# poll_anlysr_sch.net
KiCad netlist of a schematic drawn in Altium Designer
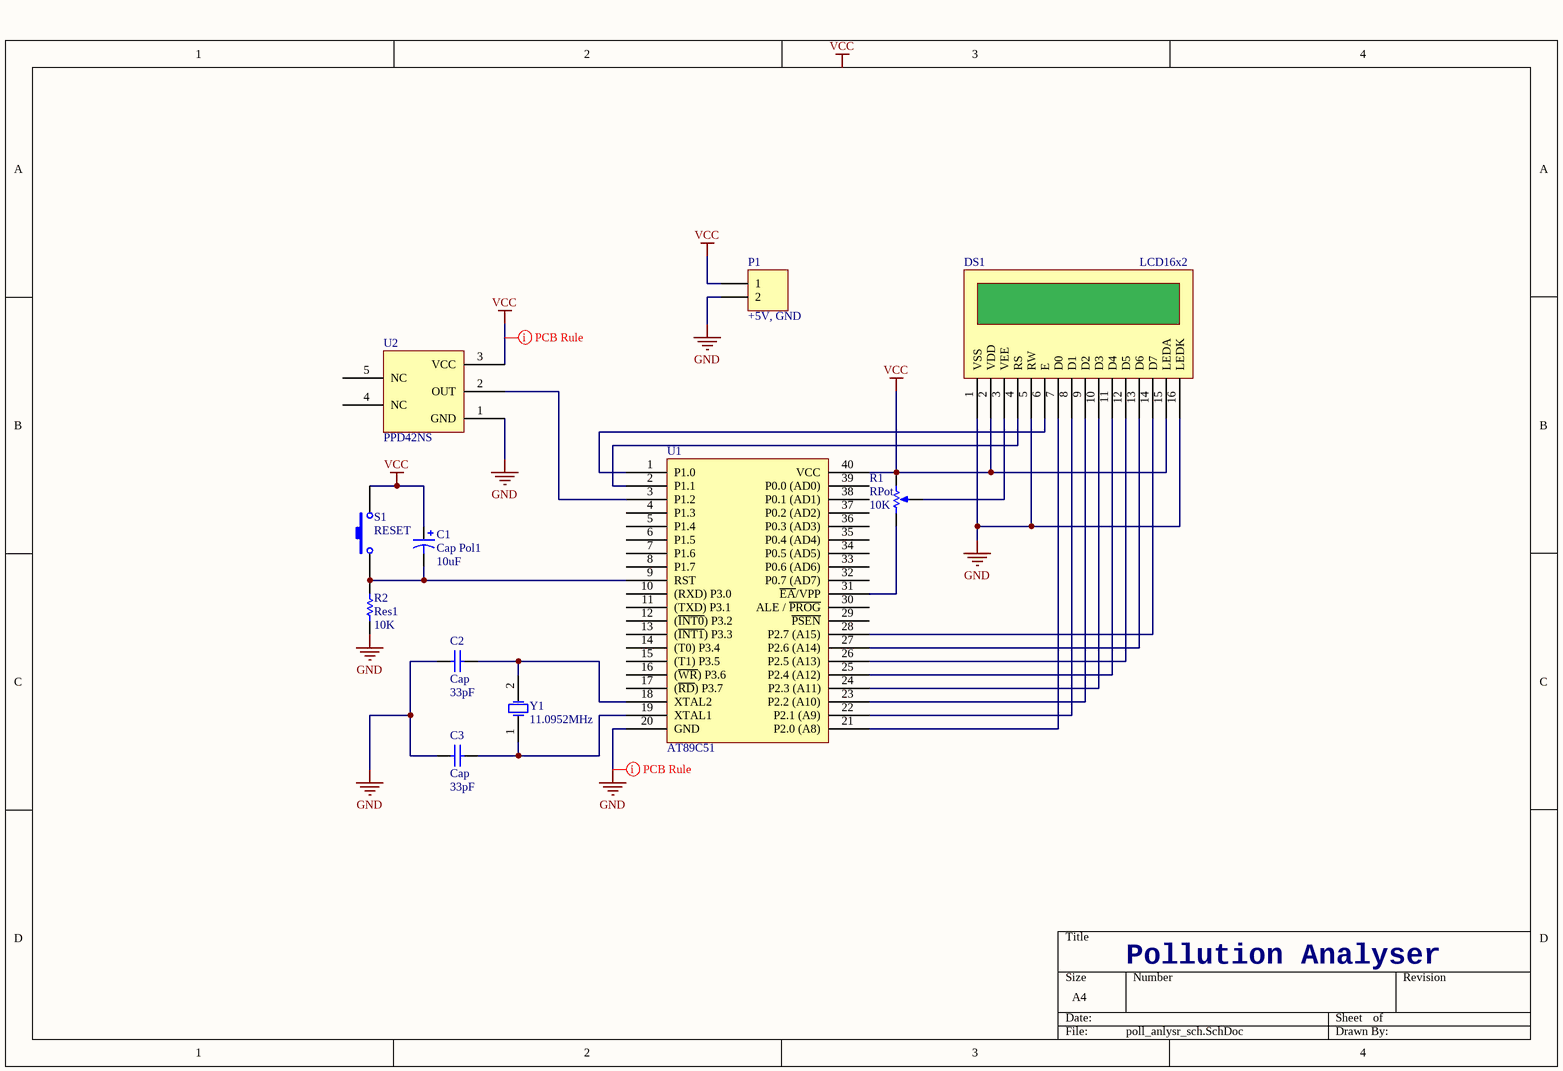
[diagram p0: poll_anlysr_sch.SchDoc]

(export (version "E")
  (design (tool "Eeschema 10.0.6"))
  (components
    (comp (ref "C1")
      (value "Cap Pol1")
      (footprint "CAPR5-4X5")
      (description "Polarized Capacitor")
      (fields (field (name "ALTIUM_VALUE") "10uF") (field (name "PUBLISHER") "Altium Limited"))
      (libsource (lib "Miscellaneous Devices") (part "Cap Pol1"))
    )
    (comp (ref "C2")
      (value "Cap")
      (footprint "CAPR5-4X5")
      (description "Capacitor")
      (fields (field (name "ALTIUM_VALUE") "33pF") (field (name "PUBLISHER") "Altium Limited"))
      (libsource (lib "Miscellaneous Devices") (part "Cap"))
    )
    (comp (ref "C3")
      (value "Cap")
      (footprint "CAPR5-4X5")
      (description "Capacitor")
      (fields (field (name "ALTIUM_VALUE") "33pF") (field (name "PUBLISHER") "Altium Limited"))
      (libsource (lib "Miscellaneous Devices") (part "Cap"))
    )
    (comp (ref "DS1")
      (value "LCD16x2")
      (footprint "LCD_16x2")
      (description "Dsiplay")
      (libsource (lib "LCD_16x2_sch") (part "LCD16x2"))
    )
    (comp (ref "P1")
      (value "+5V, GND")
      (footprint "HDR1X2")
      (description "2-Pin Header")
      (fields (field (name "PUBLISHER") "Altium Limited"))
      (libsource (lib "Miscellaneous Connectors") (part "Header 2"))
    )
    (comp (ref "R1")
      (value "RPot")
      (footprint "Rpot")
      (description "Potentiometer")
      (fields (field (name "ALTIUM_VALUE") "10K") (field (name "PUBLISHER") "Altium Limited"))
      (libsource (lib "Miscellaneous Devices") (part "RPot"))
    )
    (comp (ref "R2")
      (value "Res1")
      (footprint "AXIAL-0.3")
      (description "Resistor")
      (fields (field (name "ALTIUM_VALUE") "10K") (field (name "PUBLISHER") "Altium Limited"))
      (libsource (lib "Miscellaneous Devices") (part "Res1"))
    )
    (comp (ref "S1")
      (value "RESET")
      (footprint "SWpush")
      (description "Switch")
      (fields (field (name "PUBLISHER") "Altium Limited"))
      (libsource (lib "Miscellaneous Devices") (part "SW-PB"))
    )
    (comp (ref "U1")
      (value "AT89C51")
      (footprint "AT89C51")
      (description "8-bit uC")
      (libsource (lib "AT89C51_sch") (part "AT89C51"))
    )
    (comp (ref "U2")
      (value "PPD42NS")
      (footprint "PPD42NS")
      (description "Dust Sensor")
      (libsource (lib "PPD42NS_sch") (part "PPD42NS"))
    )
    (comp (ref "Y1")
      (value "11.0952MHz")
      (footprint "HC-49U")
      (description "Crystal Oscillator")
      (fields (field (name "PUBLISHER") "Altium Limited"))
      (libsource (lib "Miscellaneous Devices") (part "XTAL"))
    )
  )
  (nets
    (net (code "1") (name "GND") (class "Default")
      (node (ref "C2") (pin "1") (pinfunction "1_1") (pintype "passive"))
      (node (ref "C3") (pin "1") (pinfunction "1_1") (pintype "passive"))
      (node (ref "DS1") (pin "1") (pinfunction "VSS_1") (pintype "passive"))
      (node (ref "DS1") (pin "16") (pinfunction "LEDK_16") (pintype "passive"))
      (node (ref "DS1") (pin "5") (pinfunction "RW_5") (pintype "passive"))
      (node (ref "P1") (pin "2") (pinfunction "2_2") (pintype "passive"))
      (node (ref "R2") (pin "2") (pinfunction "2_2") (pintype "passive"))
      (node (ref "U1") (pin "20") (pinfunction "GND_20") (pintype "passive"))
      (node (ref "U2") (pin "1") (pinfunction "GND_1") (pintype "passive"))
    )
    (net (code "2") (name "Net-(DS1-D0)") (class "Default")
      (node (ref "DS1") (pin "7") (pinfunction "D0_7") (pintype "passive"))
      (node (ref "U1") (pin "21") (pinfunction "P2.0_(A8)_21") (pintype "passive"))
    )
    (net (code "3") (name "Net-(DS1-D1)") (class "Default")
      (node (ref "DS1") (pin "8") (pinfunction "D1_8") (pintype "passive"))
      (node (ref "U1") (pin "22") (pinfunction "P2.1_(A9)_22") (pintype "passive"))
    )
    (net (code "4") (name "Net-(DS1-D2)") (class "Default")
      (node (ref "DS1") (pin "9") (pinfunction "D2_9") (pintype "passive"))
      (node (ref "U1") (pin "23") (pinfunction "P2.2_(A10)_23") (pintype "passive"))
    )
    (net (code "5") (name "Net-(DS1-D3)") (class "Default")
      (node (ref "DS1") (pin "10") (pinfunction "D3_10") (pintype "passive"))
      (node (ref "U1") (pin "24") (pinfunction "P2.3_(A11)_24") (pintype "passive"))
    )
    (net (code "6") (name "Net-(DS1-D4)") (class "Default")
      (node (ref "DS1") (pin "11") (pinfunction "D4_11") (pintype "passive"))
      (node (ref "U1") (pin "25") (pinfunction "P2.4_(A12)_25") (pintype "passive"))
    )
    (net (code "7") (name "Net-(DS1-D5)") (class "Default")
      (node (ref "DS1") (pin "12") (pinfunction "D5_12") (pintype "passive"))
      (node (ref "U1") (pin "26") (pinfunction "P2.5_(A13)_26") (pintype "passive"))
    )
    (net (code "8") (name "Net-(DS1-D6)") (class "Default")
      (node (ref "DS1") (pin "13") (pinfunction "D6_13") (pintype "passive"))
      (node (ref "U1") (pin "27") (pinfunction "P2.6_(A14)_27") (pintype "passive"))
    )
    (net (code "9") (name "Net-(DS1-D7)") (class "Default")
      (node (ref "DS1") (pin "14") (pinfunction "D7_14") (pintype "passive"))
      (node (ref "U1") (pin "28") (pinfunction "P2.7_(A15)_28") (pintype "passive"))
    )
    (net (code "10") (name "Net-(DS1-E)") (class "Default")
      (node (ref "DS1") (pin "6") (pinfunction "E_6") (pintype "passive"))
      (node (ref "U1") (pin "1") (pinfunction "P1.0_1") (pintype "passive"))
    )
    (net (code "11") (name "Net-(DS1-RS)") (class "Default")
      (node (ref "DS1") (pin "4") (pinfunction "RS_4") (pintype "passive"))
      (node (ref "U1") (pin "2") (pinfunction "P1.1_2") (pintype "passive"))
    )
    (net (code "12") (name "Net-(DS1-VEE)") (class "Default")
      (node (ref "DS1") (pin "3") (pinfunction "VEE_3") (pintype "passive"))
      (node (ref "R1") (pin "3") (pinfunction "TAP_3") (pintype "passive"))
    )
    (net (code "13") (name "Net-(R1-TOP)") (class "Default")
      (node (ref "R1") (pin "1") (pinfunction "TOP_1") (pintype "passive"))
      (node (ref "U1") (pin "31") (pinfunction "~{EA}/VPP_31") (pintype "passive"))
    )
    (net (code "14") (name "Net-(U1-P1.2)") (class "Default")
      (node (ref "U1") (pin "3") (pinfunction "P1.2_3") (pintype "passive"))
      (node (ref "U2") (pin "2") (pinfunction "OUT_2") (pintype "passive"))
    )
    (net (code "15") (name "Net-(U1-RST)") (class "Default")
      (node (ref "C1") (pin "2") (pinfunction "2_2") (pintype "passive"))
      (node (ref "R2") (pin "1") (pinfunction "1_1") (pintype "passive"))
      (node (ref "S1") (pin "1") (pinfunction "1_1") (pintype "passive"))
      (node (ref "U1") (pin "9") (pinfunction "RST_9") (pintype "passive"))
    )
    (net (code "16") (name "Net-(U1-XTAL1)") (class "Default")
      (node (ref "C3") (pin "2") (pinfunction "2_2") (pintype "passive"))
      (node (ref "U1") (pin "19") (pinfunction "XTAL1_19") (pintype "passive"))
      (node (ref "Y1") (pin "1") (pinfunction "OSC1_1") (pintype "passive"))
    )
    (net (code "17") (name "Net-(U1-XTAL2)") (class "Default")
      (node (ref "C2") (pin "2") (pinfunction "2_2") (pintype "passive"))
      (node (ref "U1") (pin "18") (pinfunction "XTAL2_18") (pintype "passive"))
      (node (ref "Y1") (pin "2") (pinfunction "OSC2_2") (pintype "passive"))
    )
    (net (code "18") (name "VCC") (class "Default")
      (node (ref "C1") (pin "1") (pinfunction "1_1") (pintype "passive"))
      (node (ref "DS1") (pin "15") (pinfunction "LEDA_15") (pintype "passive"))
      (node (ref "DS1") (pin "2") (pinfunction "VDD_2") (pintype "passive"))
      (node (ref "P1") (pin "1") (pinfunction "1_1") (pintype "passive"))
      (node (ref "R1") (pin "2") (pinfunction "BOT_2") (pintype "passive"))
      (node (ref "S1") (pin "2") (pinfunction "2_2") (pintype "passive"))
      (node (ref "U1") (pin "40") (pinfunction "VCC_40") (pintype "passive"))
      (node (ref "U2") (pin "3") (pinfunction "VCC_3") (pintype "passive"))
    )
    (net (code "19") (name "unconnected-(U1-(RXD)_P3.0-Pad10)") (class "Default")
      (node (ref "U1") (pin "10") (pinfunction "(RXD)_P3.0_10") (pintype "passive"))
    )
    (net (code "20") (name "unconnected-(U1-(T0)_P3.4-Pad14)") (class "Default")
      (node (ref "U1") (pin "14") (pinfunction "(T0)_P3.4_14") (pintype "passive"))
    )
    (net (code "21") (name "unconnected-(U1-(T1)_P3.5-Pad15)") (class "Default")
      (node (ref "U1") (pin "15") (pinfunction "(T1)_P3.5_15") (pintype "passive"))
    )
    (net (code "22") (name "unconnected-(U1-(TXD)_P3.1-Pad11)") (class "Default")
      (node (ref "U1") (pin "11") (pinfunction "(TXD)_P3.1_11") (pintype "passive"))
    )
    (net (code "23") (name "unconnected-(U1-(~{INT0})_P3.2-Pad12)") (class "Default")
      (node (ref "U1") (pin "12") (pinfunction "(~{INT0})_P3.2_12") (pintype "passive"))
    )
    (net (code "24") (name "unconnected-(U1-(~{INT1})_P3.3-Pad13)") (class "Default")
      (node (ref "U1") (pin "13") (pinfunction "(~{INT1})_P3.3_13") (pintype "passive"))
    )
    (net (code "25") (name "unconnected-(U1-(~{RD})_P3.7-Pad17)") (class "Default")
      (node (ref "U1") (pin "17") (pinfunction "(~{RD})_P3.7_17") (pintype "passive"))
    )
    (net (code "26") (name "unconnected-(U1-(~{WR})_P3.6-Pad16)") (class "Default")
      (node (ref "U1") (pin "16") (pinfunction "(~{WR})_P3.6_16") (pintype "passive"))
    )
    (net (code "27") (name "unconnected-(U1-ALE_{slash}_~{PROG}-Pad30)") (class "Default")
      (node (ref "U1") (pin "30") (pinfunction "ALE_/_~{PROG}_30") (pintype "passive"))
    )
    (net (code "28") (name "unconnected-(U1-P0.0_(AD0)-Pad39)") (class "Default")
      (node (ref "U1") (pin "39") (pinfunction "P0.0_(AD0)_39") (pintype "passive"))
    )
    (net (code "29") (name "unconnected-(U1-P0.1_(AD1)-Pad38)") (class "Default")
      (node (ref "U1") (pin "38") (pinfunction "P0.1_(AD1)_38") (pintype "power_in"))
    )
    (net (code "30") (name "unconnected-(U1-P0.2_(AD2)-Pad37)") (class "Default")
      (node (ref "U1") (pin "37") (pinfunction "P0.2_(AD2)_37") (pintype "passive"))
    )
    (net (code "31") (name "unconnected-(U1-P0.3_(AD3)-Pad36)") (class "Default")
      (node (ref "U1") (pin "36") (pinfunction "P0.3_(AD3)_36") (pintype "passive"))
    )
    (net (code "32") (name "unconnected-(U1-P0.4_(AD4)-Pad35)") (class "Default")
      (node (ref "U1") (pin "35") (pinfunction "P0.4_(AD4)_35") (pintype "passive"))
    )
    (net (code "33") (name "unconnected-(U1-P0.5_(AD5)-Pad34)") (class "Default")
      (node (ref "U1") (pin "34") (pinfunction "P0.5_(AD5)_34") (pintype "passive"))
    )
    (net (code "34") (name "unconnected-(U1-P0.6_(AD6)-Pad33)") (class "Default")
      (node (ref "U1") (pin "33") (pinfunction "P0.6_(AD6)_33") (pintype "passive"))
    )
    (net (code "35") (name "unconnected-(U1-P0.7_(AD7)-Pad32)") (class "Default")
      (node (ref "U1") (pin "32") (pinfunction "P0.7_(AD7)_32") (pintype "passive"))
    )
    (net (code "36") (name "unconnected-(U1-P1.3-Pad4)") (class "Default")
      (node (ref "U1") (pin "4") (pinfunction "P1.3_4") (pintype "passive"))
    )
    (net (code "37") (name "unconnected-(U1-P1.4-Pad5)") (class "Default")
      (node (ref "U1") (pin "5") (pinfunction "P1.4_5") (pintype "passive"))
    )
    (net (code "38") (name "unconnected-(U1-P1.5-Pad6)") (class "Default")
      (node (ref "U1") (pin "6") (pinfunction "P1.5_6") (pintype "passive"))
    )
    (net (code "39") (name "unconnected-(U1-P1.6-Pad7)") (class "Default")
      (node (ref "U1") (pin "7") (pinfunction "P1.6_7") (pintype "passive"))
    )
    (net (code "40") (name "unconnected-(U1-P1.7-Pad8)") (class "Default")
      (node (ref "U1") (pin "8") (pinfunction "P1.7_8") (pintype "passive"))
    )
    (net (code "41") (name "unconnected-(U1-~{PSEN}-Pad29)") (class "Default")
      (node (ref "U1") (pin "29") (pinfunction "~{PSEN}_29") (pintype "passive"))
    )
    (net (code "42") (name "unconnected-(U2-NC-Pad4)") (class "Default")
      (node (ref "U2") (pin "4") (pinfunction "NC_4") (pintype "passive"))
    )
    (net (code "43") (name "unconnected-(U2-NC-Pad5)") (class "Default")
      (node (ref "U2") (pin "5") (pinfunction "NC_5") (pintype "passive"))
    )
  )
)
